# Acond_Elec.net
KiCad netlist of a schematic drawn in Altium Designer
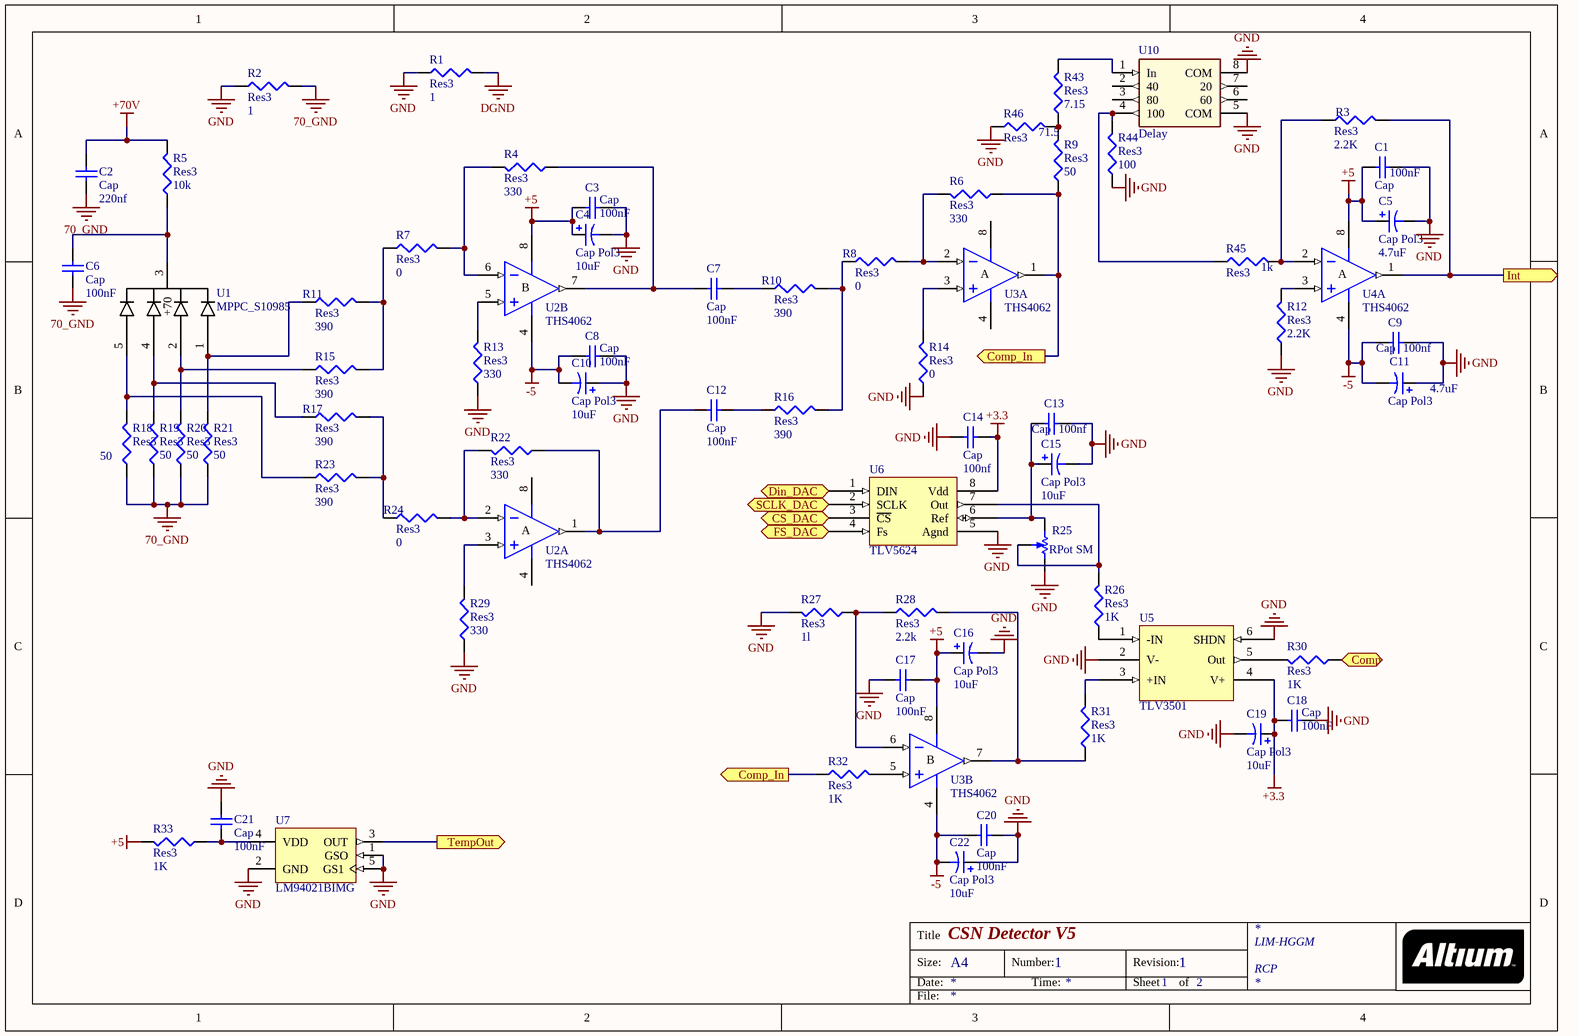
[diagram p0: Acond_Elec.SchDoc]

(export (version "E")
  (design (tool "Eeschema 10.0.6"))
  (components
    (comp (ref "C1")
      (value "Cap")
      (footprint "J1-0603")
      (description "Capacitor")
      (fields (field (name "ALTIUM_VALUE") "100nF") (field (name "PUBLISHER") "Altium Limited"))
      (libsource (lib "Miscellaneous Devices") (part "Cap"))
    )
    (comp (ref "C2")
      (value "Cap")
      (footprint "C0805")
      (description "Capacitor")
      (fields (field (name "ALTIUM_VALUE") "220nf") (field (name "PUBLISHER") "Altium Limited"))
      (libsource (lib "Miscellaneous Devices") (part "Cap"))
    )
    (comp (ref "C3")
      (value "Cap")
      (footprint "J1-0603")
      (description "Capacitor")
      (fields (field (name "ALTIUM_VALUE") "100nF") (field (name "PUBLISHER") "Altium Limited"))
      (libsource (lib "Miscellaneous Devices") (part "Cap"))
    )
    (comp (ref "C4")
      (value "Cap Pol3")
      (footprint "6-0805_N")
      (description "Polarized Capacitor (Surface Mount)")
      (fields (field (name "ALTIUM_VALUE") "10uF") (field (name "PUBLISHER") "Altium Limited"))
      (libsource (lib "Miscellaneous Devices") (part "Cap Pol3"))
    )
    (comp (ref "C5")
      (value "Cap Pol3")
      (footprint "6-0805_N")
      (description "Polarized Capacitor (Surface Mount)")
      (fields (field (name "ALTIUM_VALUE") "4.7uF") (field (name "PUBLISHER") "Altium Limited"))
      (libsource (lib "Miscellaneous Devices") (part "Cap Pol3"))
    )
    (comp (ref "C6")
      (value "Cap")
      (footprint "C0805")
      (description "Capacitor")
      (fields (field (name "ALTIUM_VALUE") "100nF") (field (name "PUBLISHER") "Altium Limited"))
      (libsource (lib "Miscellaneous Devices") (part "Cap"))
    )
    (comp (ref "C7")
      (value "Cap")
      (footprint "J1-0603")
      (description "Capacitor")
      (fields (field (name "ALTIUM_VALUE") "100nF") (field (name "PUBLISHER") "Altium Limited"))
      (libsource (lib "Miscellaneous Devices") (part "Cap"))
    )
    (comp (ref "C8")
      (value "Cap")
      (footprint "J1-0603")
      (description "Capacitor")
      (fields (field (name "ALTIUM_VALUE") "100nF") (field (name "PUBLISHER") "Altium Limited"))
      (libsource (lib "Miscellaneous Devices") (part "Cap"))
    )
    (comp (ref "C9")
      (value "Cap")
      (footprint "J1-0603")
      (description "Capacitor")
      (fields (field (name "ALTIUM_VALUE") "100nf") (field (name "PUBLISHER") "Altium Limited"))
      (libsource (lib "Miscellaneous Devices") (part "Cap"))
    )
    (comp (ref "C10")
      (value "Cap Pol3")
      (footprint "6-0805_N")
      (description "Polarized Capacitor (Surface Mount)")
      (fields (field (name "ALTIUM_VALUE") "10uF") (field (name "PUBLISHER") "Altium Limited"))
      (libsource (lib "Miscellaneous Devices") (part "Cap Pol3"))
    )
    (comp (ref "C11")
      (value "Cap Pol3")
      (footprint "6-0805_N")
      (description "Polarized Capacitor (Surface Mount)")
      (fields (field (name "ALTIUM_VALUE") "4.7uF") (field (name "PUBLISHER") "Altium Limited"))
      (libsource (lib "Miscellaneous Devices") (part "Cap Pol3"))
    )
    (comp (ref "C12")
      (value "Cap")
      (footprint "J1-0603")
      (description "Capacitor")
      (fields (field (name "ALTIUM_VALUE") "100nF") (field (name "PUBLISHER") "Altium Limited"))
      (libsource (lib "Miscellaneous Devices") (part "Cap"))
    )
    (comp (ref "C13")
      (value "Cap")
      (footprint "J1-0603")
      (description "Capacitor")
      (fields (field (name "ALTIUM_VALUE") "100nf") (field (name "PUBLISHER") "Altium Limited"))
      (libsource (lib "Miscellaneous Devices") (part "Cap"))
    )
    (comp (ref "C14")
      (value "Cap")
      (footprint "J1-0603")
      (description "Capacitor")
      (fields (field (name "ALTIUM_VALUE") "100nf") (field (name "PUBLISHER") "Altium Limited"))
      (libsource (lib "Miscellaneous Devices") (part "Cap"))
    )
    (comp (ref "C15")
      (value "Cap Pol3")
      (footprint "6-0805_N")
      (description "Polarized Capacitor (Surface Mount)")
      (fields (field (name "ALTIUM_VALUE") "10uF") (field (name "PUBLISHER") "Altium Limited"))
      (libsource (lib "Miscellaneous Devices") (part "Cap Pol3"))
    )
    (comp (ref "C16")
      (value "Cap Pol3")
      (footprint "6-0805_N")
      (description "Polarized Capacitor (Surface Mount)")
      (fields (field (name "ALTIUM_VALUE") "10uF") (field (name "PUBLISHER") "Altium Limited"))
      (libsource (lib "Miscellaneous Devices") (part "Cap Pol3"))
    )
    (comp (ref "C17")
      (value "Cap")
      (footprint "J1-0603")
      (description "Capacitor")
      (fields (field (name "ALTIUM_VALUE") "100nF") (field (name "PUBLISHER") "Altium Limited"))
      (libsource (lib "Miscellaneous Devices") (part "Cap"))
    )
    (comp (ref "C18")
      (value "Cap")
      (footprint "J1-0603")
      (description "Capacitor")
      (fields (field (name "ALTIUM_VALUE") "100nF") (field (name "PUBLISHER") "Altium Limited"))
      (libsource (lib "Miscellaneous Devices") (part "Cap"))
    )
    (comp (ref "C19")
      (value "Cap Pol3")
      (footprint "6-0805_N")
      (description "Polarized Capacitor (Surface Mount)")
      (fields (field (name "ALTIUM_VALUE") "10uF") (field (name "PUBLISHER") "Altium Limited"))
      (libsource (lib "Miscellaneous Devices") (part "Cap Pol3"))
    )
    (comp (ref "C20")
      (value "Cap")
      (footprint "J1-0603")
      (description "Capacitor")
      (fields (field (name "ALTIUM_VALUE") "100nF") (field (name "PUBLISHER") "Altium Limited"))
      (libsource (lib "Miscellaneous Devices") (part "Cap"))
    )
    (comp (ref "C21")
      (value "Cap")
      (footprint "6-0805_N")
      (description "Capacitor")
      (fields (field (name "ALTIUM_VALUE") "100nF") (field (name "PUBLISHER") "Altium Limited"))
      (libsource (lib "Miscellaneous Devices") (part "Cap"))
    )
    (comp (ref "C22")
      (value "Cap Pol3")
      (footprint "6-0805_N")
      (description "Polarized Capacitor (Surface Mount)")
      (fields (field (name "ALTIUM_VALUE") "10uF") (field (name "PUBLISHER") "Altium Limited"))
      (libsource (lib "Miscellaneous Devices") (part "Cap Pol3"))
    )
    (comp (ref "R1")
      (value "Res3")
      (footprint "J1-0603")
      (description "Resistor")
      (fields (field (name "ALTIUM_VALUE") "1") (field (name "PUBLISHER") "Altium Limited"))
      (libsource (lib "Miscellaneous Devices") (part "Res3"))
    )
    (comp (ref "R2")
      (value "Res3")
      (footprint "J1-0603")
      (description "Resistor")
      (fields (field (name "ALTIUM_VALUE") "1") (field (name "PUBLISHER") "Altium Limited"))
      (libsource (lib "Miscellaneous Devices") (part "Res3"))
    )
    (comp (ref "R3")
      (value "Res3")
      (footprint "J1-0603")
      (description "Resistor")
      (fields (field (name "ALTIUM_VALUE") "2.2K") (field (name "PUBLISHER") "Altium Limited"))
      (libsource (lib "Miscellaneous Devices") (part "Res3"))
    )
    (comp (ref "R4")
      (value "Res3")
      (footprint "J1-0603")
      (description "Resistor")
      (fields (field (name "ALTIUM_VALUE") "330") (field (name "PUBLISHER") "Altium Limited"))
      (libsource (lib "Miscellaneous Devices") (part "Res3"))
    )
    (comp (ref "R5")
      (value "Res3")
      (footprint "J1-0603")
      (description "Resistor")
      (fields (field (name "ALTIUM_VALUE") "10k") (field (name "PUBLISHER") "Altium Limited"))
      (libsource (lib "Miscellaneous Devices") (part "Res3"))
    )
    (comp (ref "R6")
      (value "Res3")
      (footprint "J1-0603")
      (description "Resistor")
      (fields (field (name "ALTIUM_VALUE") "330") (field (name "PUBLISHER") "Altium Limited"))
      (libsource (lib "Miscellaneous Devices") (part "Res3"))
    )
    (comp (ref "R7")
      (value "Res3")
      (footprint "J1-0603")
      (description "Resistor")
      (fields (field (name "ALTIUM_VALUE") "0") (field (name "PUBLISHER") "Altium Limited"))
      (libsource (lib "Miscellaneous Devices") (part "Res3"))
    )
    (comp (ref "R8")
      (value "Res3")
      (footprint "J1-0603")
      (description "Resistor")
      (fields (field (name "ALTIUM_VALUE") "0") (field (name "PUBLISHER") "Altium Limited"))
      (libsource (lib "Miscellaneous Devices") (part "Res3"))
    )
    (comp (ref "R9")
      (value "Res3")
      (footprint "J1-0603")
      (description "Resistor")
      (fields (field (name "ALTIUM_VALUE") "50") (field (name "PUBLISHER") "Altium Limited"))
      (libsource (lib "Miscellaneous Devices") (part "Res3"))
    )
    (comp (ref "R10")
      (value "Res3")
      (footprint "J1-0603")
      (description "Resistor")
      (fields (field (name "ALTIUM_VALUE") "390") (field (name "PUBLISHER") "Altium Limited"))
      (libsource (lib "Miscellaneous Devices") (part "Res3"))
    )
    (comp (ref "R11")
      (value "Res3")
      (footprint "J1-0603")
      (description "Resistor")
      (fields (field (name "ALTIUM_VALUE") "390") (field (name "PUBLISHER") "Altium Limited"))
      (libsource (lib "Miscellaneous Devices") (part "Res3"))
    )
    (comp (ref "R12")
      (value "Res3")
      (footprint "J1-0603")
      (description "Resistor")
      (fields (field (name "ALTIUM_VALUE") "2.2K") (field (name "PUBLISHER") "Altium Limited"))
      (libsource (lib "Miscellaneous Devices") (part "Res3"))
    )
    (comp (ref "R13")
      (value "Res3")
      (footprint "J1-0603")
      (description "Resistor")
      (fields (field (name "ALTIUM_VALUE") "330") (field (name "PUBLISHER") "Altium Limited"))
      (libsource (lib "Miscellaneous Devices") (part "Res3"))
    )
    (comp (ref "R14")
      (value "Res3")
      (footprint "J1-0603")
      (description "Resistor")
      (fields (field (name "ALTIUM_VALUE") "0") (field (name "PUBLISHER") "Altium Limited"))
      (libsource (lib "Miscellaneous Devices") (part "Res3"))
    )
    (comp (ref "R15")
      (value "Res3")
      (footprint "J1-0603")
      (description "Resistor")
      (fields (field (name "ALTIUM_VALUE") "390") (field (name "PUBLISHER") "Altium Limited"))
      (libsource (lib "Miscellaneous Devices") (part "Res3"))
    )
    (comp (ref "R16")
      (value "Res3")
      (footprint "J1-0603")
      (description "Resistor")
      (fields (field (name "ALTIUM_VALUE") "390") (field (name "PUBLISHER") "Altium Limited"))
      (libsource (lib "Miscellaneous Devices") (part "Res3"))
    )
    (comp (ref "R17")
      (value "Res3")
      (footprint "J1-0603")
      (description "Resistor")
      (fields (field (name "ALTIUM_VALUE") "390") (field (name "PUBLISHER") "Altium Limited"))
      (libsource (lib "Miscellaneous Devices") (part "Res3"))
    )
    (comp (ref "R18")
      (value "Res3")
      (footprint "J1-0603")
      (description "Resistor")
      (fields (field (name "ALTIUM_VALUE") "50") (field (name "PUBLISHER") "Altium Limited"))
      (libsource (lib "Miscellaneous Devices") (part "Res3"))
    )
    (comp (ref "R19")
      (value "Res3")
      (footprint "J1-0603")
      (description "Resistor")
      (fields (field (name "ALTIUM_VALUE") "50") (field (name "PUBLISHER") "Altium Limited"))
      (libsource (lib "Miscellaneous Devices") (part "Res3"))
    )
    (comp (ref "R20")
      (value "Res3")
      (footprint "J1-0603")
      (description "Resistor")
      (fields (field (name "ALTIUM_VALUE") "50") (field (name "PUBLISHER") "Altium Limited"))
      (libsource (lib "Miscellaneous Devices") (part "Res3"))
    )
    (comp (ref "R21")
      (value "Res3")
      (footprint "J1-0603")
      (description "Resistor")
      (fields (field (name "ALTIUM_VALUE") "50") (field (name "PUBLISHER") "Altium Limited"))
      (libsource (lib "Miscellaneous Devices") (part "Res3"))
    )
    (comp (ref "R22")
      (value "Res3")
      (footprint "J1-0603")
      (description "Resistor")
      (fields (field (name "ALTIUM_VALUE") "330") (field (name "PUBLISHER") "Altium Limited"))
      (libsource (lib "Miscellaneous Devices") (part "Res3"))
    )
    (comp (ref "R23")
      (value "Res3")
      (footprint "J1-0603")
      (description "Resistor")
      (fields (field (name "ALTIUM_VALUE") "390") (field (name "PUBLISHER") "Altium Limited"))
      (libsource (lib "Miscellaneous Devices") (part "Res3"))
    )
    (comp (ref "R24")
      (value "Res3")
      (footprint "J1-0603")
      (description "Resistor")
      (fields (field (name "ALTIUM_VALUE") "0") (field (name "PUBLISHER") "Altium Limited"))
      (libsource (lib "Miscellaneous Devices") (part "Res3"))
    )
    (comp (ref "R25")
      (value "RPot SM")
      (footprint "POT4MM-2")
      (description "Square Trimming Potentiometer")
      (fields (field (name "PUBLISHER") "Altium Limited"))
      (libsource (lib "Miscellaneous Devices") (part "RPot SM"))
    )
    (comp (ref "R26")
      (value "Res3")
      (footprint "J1-0603")
      (description "Resistor")
      (fields (field (name "ALTIUM_VALUE") "1K") (field (name "PUBLISHER") "Altium Limited"))
      (libsource (lib "Miscellaneous Devices") (part "Res3"))
    )
    (comp (ref "R27")
      (value "Res3")
      (footprint "J1-0603")
      (description "Resistor")
      (fields (field (name "ALTIUM_VALUE") "1l") (field (name "PUBLISHER") "Altium Limited"))
      (libsource (lib "Miscellaneous Devices") (part "Res3"))
    )
    (comp (ref "R28")
      (value "Res3")
      (footprint "J1-0603")
      (description "Resistor")
      (fields (field (name "ALTIUM_VALUE") "2.2k") (field (name "PUBLISHER") "Altium Limited"))
      (libsource (lib "Miscellaneous Devices") (part "Res3"))
    )
    (comp (ref "R29")
      (value "Res3")
      (footprint "J1-0603")
      (description "Resistor")
      (fields (field (name "ALTIUM_VALUE") "330") (field (name "PUBLISHER") "Altium Limited"))
      (libsource (lib "Miscellaneous Devices") (part "Res3"))
    )
    (comp (ref "R30")
      (value "Res3")
      (footprint "J1-0603")
      (description "Resistor")
      (fields (field (name "ALTIUM_VALUE") "1K") (field (name "PUBLISHER") "Altium Limited"))
      (libsource (lib "Miscellaneous Devices") (part "Res3"))
    )
    (comp (ref "R31")
      (value "Res3")
      (footprint "J1-0603")
      (description "Resistor")
      (fields (field (name "ALTIUM_VALUE") "1K") (field (name "PUBLISHER") "Altium Limited"))
      (libsource (lib "Miscellaneous Devices") (part "Res3"))
    )
    (comp (ref "R32")
      (value "Res3")
      (footprint "J1-0603")
      (description "Resistor")
      (fields (field (name "ALTIUM_VALUE") "1K") (field (name "PUBLISHER") "Altium Limited"))
      (libsource (lib "Miscellaneous Devices") (part "Res3"))
    )
    (comp (ref "R33")
      (value "Res3")
      (footprint "J1-0603")
      (description "Resistor")
      (fields (field (name "ALTIUM_VALUE") "1K") (field (name "PUBLISHER") "Altium Limited"))
      (libsource (lib "Miscellaneous Devices") (part "Res3"))
    )
    (comp (ref "R43")
      (value "Res3")
      (footprint "J1-0603")
      (description "Resistor")
      (fields (field (name "ALTIUM_VALUE") "7.15") (field (name "PUBLISHER") "Altium Limited"))
      (libsource (lib "Miscellaneous Devices") (part "Res3"))
    )
    (comp (ref "R44")
      (value "Res3")
      (footprint "J1-0603")
      (description "Resistor")
      (fields (field (name "ALTIUM_VALUE") "100") (field (name "PUBLISHER") "Altium Limited"))
      (libsource (lib "Miscellaneous Devices") (part "Res3"))
    )
    (comp (ref "R45")
      (value "Res3")
      (footprint "J1-0603")
      (description "Resistor")
      (fields (field (name "ALTIUM_VALUE") "1k") (field (name "PUBLISHER") "Altium Limited"))
      (libsource (lib "Miscellaneous Devices") (part "Res3"))
    )
    (comp (ref "R46")
      (value "Res3")
      (footprint "J1-0603")
      (description "Resistor")
      (fields (field (name "ALTIUM_VALUE") "71.5") (field (name "PUBLISHER") "Altium Limited"))
      (libsource (lib "Miscellaneous Devices") (part "Res3"))
    )
    (comp (ref "U1")
      (value "MPPC_S10985")
      (footprint "S10985_HAM")
      (libsource (lib "Int_Lib1") (part "MPPC_S10985"))
    )
    (comp (ref "U2")
      (value "THS4062")
      (footprint "SO-8_N")
      (description "Dual 600MHz, 50mW Current Feedback Amplifier")
      (fields (field (name "PUBLISHER") "Altium Limited"))
      (libsource (lib "AD Operational Amplifier") (part "AD8002AR"))
    )
    (comp (ref "U3")
      (value "THS4062")
      (footprint "SO-8_N")
      (description "Dual 600MHz, 50mW Current Feedback Amplifier")
      (fields (field (name "PUBLISHER") "Altium Limited"))
      (libsource (lib "AD Operational Amplifier") (part "AD8002AR"))
    )
    (comp (ref "U4")
      (value "THS4062")
      (footprint "SO-8_N")
      (description "Dual 600MHz, 50mW Current Feedback Amplifier")
      (fields (field (name "PUBLISHER") "Altium Limited"))
      (libsource (lib "AD Operational Amplifier") (part "AD8002AR"))
    )
    (comp (ref "U5")
      (value "TLV3501")
      (footprint "SOT23-6_N")
      (description "Analog Comparator")
      (libsource (lib "Int_Lib1") (part "TLV3501"))
    )
    (comp (ref "U6")
      (value "TLV5624")
      (footprint "SO-8_N")
      (description "DAC, internal reference, SPI")
      (libsource (lib "Int_Lib1") (part "TLV5624"))
    )
    (comp (ref "U7")
      (value "LM94021BIMG")
      (footprint "MAA05A_N")
      (description "Multi-Gain Analog Temperature Sensor, 5-pin SC-70")
      (fields
        (field (name "MANUFACTURER") "National Semiconductor")
        (field (name "PUBLISHER") "Altium Limited")
      )
      (libsource (lib "NSC Temperature Sensor") (part "LM94021BIMG"))
    )
    (comp (ref "U10") (value "Delay") (footprint "AMZ-G-SMD") (libsource (lib "Int_Lib1") (part "AMZ-601G")))
  )
  (nets
    (net (code "1") (name "+3.3") (class "Default")
      (node (ref "C14") (pin "1") (pinfunction "1_1") (pintype "passive"))
      (node (ref "C18") (pin "2") (pinfunction "2_2") (pintype "passive"))
      (node (ref "C19") (pin "1") (pinfunction "1_1") (pintype "passive"))
      (node (ref "U5") (pin "4") (pinfunction "V+_4") (pintype "power_in"))
      (node (ref "U6") (pin "8") (pinfunction "Vdd_8") (pintype "power_in"))
    )
    (net (code "2") (name "+5") (class "Default")
      (node (ref "C1") (pin "2") (pinfunction "2_2") (pintype "passive"))
      (node (ref "C16") (pin "1") (pinfunction "1_1") (pintype "passive"))
      (node (ref "C17") (pin "2") (pinfunction "2_2") (pintype "passive"))
      (node (ref "C3") (pin "2") (pinfunction "2_2") (pintype "passive"))
      (node (ref "C4") (pin "1") (pinfunction "1_1") (pintype "passive"))
      (node (ref "C5") (pin "1") (pinfunction "1_1") (pintype "passive"))
      (node (ref "R33") (pin "2") (pinfunction "2_2") (pintype "passive"))
      (node (ref "U2") (pin "8") (pinfunction "V+_8") (pintype "power_in"))
      (node (ref "U3") (pin "8") (pinfunction "V+_8") (pintype "power_in"))
      (node (ref "U4") (pin "8") (pinfunction "V+_8") (pintype "power_in"))
    )
    (net (code "3") (name "+70V") (class "Default")
      (node (ref "C2") (pin "2") (pinfunction "2_2") (pintype "passive"))
      (node (ref "R5") (pin "2") (pinfunction "2_2") (pintype "passive"))
    )
    (net (code "4") (name "-5") (class "Default")
      (node (ref "C10") (pin "2") (pinfunction "2_2") (pintype "passive"))
      (node (ref "C11") (pin "2") (pinfunction "2_2") (pintype "passive"))
      (node (ref "C20") (pin "1") (pinfunction "1_1") (pintype "passive"))
      (node (ref "C22") (pin "2") (pinfunction "2_2") (pintype "passive"))
      (node (ref "C8") (pin "2") (pinfunction "2_2") (pintype "passive"))
      (node (ref "C9") (pin "1") (pinfunction "1_1") (pintype "passive"))
      (node (ref "U2") (pin "4") (pinfunction "V-_4") (pintype "power_in"))
      (node (ref "U3") (pin "4") (pinfunction "V-_4") (pintype "power_in"))
      (node (ref "U4") (pin "4") (pinfunction "V-_4") (pintype "power_in"))
    )
    (net (code "5") (name "/CS_DAC") (class "Default")
      (node (ref "U6") (pin "3") (pinfunction "~{CS}_3") (pintype "passive"))
    )
    (net (code "6") (name "/Comp") (class "Default")
      (node (ref "R30") (pin "1") (pinfunction "1_1") (pintype "passive"))
    )
    (net (code "7") (name "/Comp_In") (class "Default")
      (node (ref "R32") (pin "1") (pinfunction "1_1") (pintype "passive"))
      (node (ref "R6") (pin "1") (pinfunction "1_1") (pintype "passive"))
      (node (ref "R9") (pin "1") (pinfunction "1_1") (pintype "passive"))
      (node (ref "U3") (pin "1") (pinfunction "OUT_1") (pintype "output"))
    )
    (net (code "8") (name "/Din_DAC") (class "Default")
      (node (ref "U6") (pin "1") (pinfunction "DIN_1") (pintype "input"))
    )
    (net (code "9") (name "/FS_DAC") (class "Default")
      (node (ref "U6") (pin "4") (pinfunction "Fs_4") (pintype "input"))
    )
    (net (code "10") (name "/Int") (class "Default")
      (node (ref "R3") (pin "2") (pinfunction "2_2") (pintype "passive"))
      (node (ref "U4") (pin "1") (pinfunction "OUT_1") (pintype "output"))
    )
    (net (code "11") (name "/SCLK_DAC") (class "Default")
      (node (ref "U6") (pin "2") (pinfunction "SCLK_2") (pintype "input"))
    )
    (net (code "12") (name "/TempOut") (class "Default")
      (node (ref "U7") (pin "3") (pinfunction "OUT_3") (pintype "output"))
    )
    (net (code "13") (name "70_GND") (class "Default")
      (node (ref "C2") (pin "1") (pinfunction "1_1") (pintype "passive"))
      (node (ref "C6") (pin "1") (pinfunction "1_1") (pintype "passive"))
      (node (ref "R18") (pin "1") (pinfunction "1_1") (pintype "passive"))
      (node (ref "R19") (pin "1") (pinfunction "1_1") (pintype "passive"))
      (node (ref "R2") (pin "2") (pinfunction "2_2") (pintype "passive"))
      (node (ref "R20") (pin "1") (pinfunction "1_1") (pintype "passive"))
      (node (ref "R21") (pin "1") (pinfunction "1_1") (pintype "passive"))
    )
    (net (code "14") (name "DGND") (class "Default")
      (node (ref "R1") (pin "2") (pinfunction "2_2") (pintype "passive"))
    )
    (net (code "15") (name "GND") (class "Default")
      (node (ref "C1") (pin "1") (pinfunction "1_1") (pintype "passive"))
      (node (ref "C10") (pin "1") (pinfunction "1_1") (pintype "passive"))
      (node (ref "C11") (pin "1") (pinfunction "1_1") (pintype "passive"))
      (node (ref "C13") (pin "2") (pinfunction "2_2") (pintype "passive"))
      (node (ref "C14") (pin "2") (pinfunction "2_2") (pintype "passive"))
      (node (ref "C15") (pin "2") (pinfunction "2_2") (pintype "passive"))
      (node (ref "C16") (pin "2") (pinfunction "2_2") (pintype "passive"))
      (node (ref "C17") (pin "1") (pinfunction "1_1") (pintype "passive"))
      (node (ref "C18") (pin "1") (pinfunction "1_1") (pintype "passive"))
      (node (ref "C19") (pin "2") (pinfunction "2_2") (pintype "passive"))
      (node (ref "C20") (pin "2") (pinfunction "2_2") (pintype "passive"))
      (node (ref "C21") (pin "1") (pinfunction "1_1") (pintype "passive"))
      (node (ref "C22") (pin "1") (pinfunction "1_1") (pintype "passive"))
      (node (ref "C3") (pin "1") (pinfunction "1_1") (pintype "passive"))
      (node (ref "C4") (pin "2") (pinfunction "2_2") (pintype "passive"))
      (node (ref "C5") (pin "2") (pinfunction "2_2") (pintype "passive"))
      (node (ref "C8") (pin "1") (pinfunction "1_1") (pintype "passive"))
      (node (ref "C9") (pin "2") (pinfunction "2_2") (pintype "passive"))
      (node (ref "R1") (pin "1") (pinfunction "1_1") (pintype "passive"))
      (node (ref "R12") (pin "1") (pinfunction "1_1") (pintype "passive"))
      (node (ref "R13") (pin "1") (pinfunction "1_1") (pintype "passive"))
      (node (ref "R14") (pin "1") (pinfunction "1_1") (pintype "passive"))
      (node (ref "R2") (pin "1") (pinfunction "1_1") (pintype "passive"))
      (node (ref "R25") (pin "CW") (pinfunction "+_CW") (pintype "passive"))
      (node (ref "R27") (pin "2") (pinfunction "2_2") (pintype "passive"))
      (node (ref "R29") (pin "1") (pinfunction "1_1") (pintype "passive"))
      (node (ref "R44") (pin "1") (pinfunction "1_1") (pintype "passive"))
      (node (ref "R46") (pin "1") (pinfunction "1_1") (pintype "passive"))
      (node (ref "U10") (pin "5") (pinfunction "COM_5") (pintype "power_in"))
      (node (ref "U10") (pin "8") (pinfunction "COM_8") (pintype "power_in"))
      (node (ref "U5") (pin "2") (pinfunction "V-_2") (pintype "power_in"))
      (node (ref "U5") (pin "6") (pinfunction "SHDN_6") (pintype "input"))
      (node (ref "U6") (pin "5") (pinfunction "Agnd_5") (pintype "power_in"))
      (node (ref "U7") (pin "1") (pinfunction "GSO_1") (pintype "input"))
      (node (ref "U7") (pin "2") (pinfunction "GND_2") (pintype "power_in"))
      (node (ref "U7") (pin "5") (pinfunction "GS1_5") (pintype "input"))
    )
    (net (code "16") (name "Net-(C7-Pad2)") (class "Default")
      (node (ref "C7") (pin "2") (pinfunction "2_2") (pintype "passive"))
      (node (ref "R10") (pin "1") (pinfunction "1_1") (pintype "passive"))
    )
    (net (code "17") (name "Net-(C12-Pad2)") (class "Default")
      (node (ref "C12") (pin "2") (pinfunction "2_2") (pintype "passive"))
      (node (ref "R16") (pin "1") (pinfunction "1_1") (pintype "passive"))
    )
    (net (code "18") (name "Net-(R10-Pad2)") (class "Default")
      (node (ref "R10") (pin "2") (pinfunction "2_2") (pintype "passive"))
      (node (ref "R16") (pin "2") (pinfunction "2_2") (pintype "passive"))
      (node (ref "R8") (pin "1") (pinfunction "1_1") (pintype "passive"))
    )
    (net (code "19") (name "Net-(R11-Pad2)") (class "Default")
      (node (ref "R11") (pin "2") (pinfunction "2_2") (pintype "passive"))
      (node (ref "R15") (pin "2") (pinfunction "2_2") (pintype "passive"))
      (node (ref "R7") (pin "1") (pinfunction "1_1") (pintype "passive"))
    )
    (net (code "20") (name "Net-(R17-Pad1)") (class "Default")
      (node (ref "R17") (pin "1") (pinfunction "1_1") (pintype "passive"))
      (node (ref "R19") (pin "2") (pinfunction "2_2") (pintype "passive"))
      (node (ref "U1") (pin "4") (pinfunction "4_4") (pintype "passive"))
    )
    (net (code "21") (name "Net-(R17-Pad2)") (class "Default")
      (node (ref "R17") (pin "2") (pinfunction "2_2") (pintype "passive"))
      (node (ref "R23") (pin "2") (pinfunction "2_2") (pintype "passive"))
      (node (ref "R24") (pin "1") (pinfunction "1_1") (pintype "passive"))
    )
    (net (code "22") (name "Net-(R18-Pad2)") (class "Default")
      (node (ref "R18") (pin "2") (pinfunction "2_2") (pintype "passive"))
      (node (ref "R23") (pin "1") (pinfunction "1_1") (pintype "passive"))
      (node (ref "U1") (pin "5") (pinfunction "5_5") (pintype "passive"))
    )
    (net (code "23") (name "Net-(R25--)") (class "Default")
      (node (ref "C13") (pin "1") (pinfunction "1_1") (pintype "passive"))
      (node (ref "C15") (pin "1") (pinfunction "1_1") (pintype "passive"))
      (node (ref "R25") (pin "CCW") (pinfunction "-_CCW") (pintype "passive"))
      (node (ref "U6") (pin "6") (pinfunction "Ref_6") (pintype "bidirectional"))
    )
    (net (code "24") (name "Net-(R43-Pad1)") (class "Default")
      (node (ref "R43") (pin "1") (pinfunction "1_1") (pintype "passive"))
      (node (ref "R46") (pin "2") (pinfunction "2_2") (pintype "passive"))
      (node (ref "R9") (pin "2") (pinfunction "2_2") (pintype "passive"))
    )
    (net (code "25") (name "Net-(U1-+70)") (class "Default")
      (node (ref "C6") (pin "2") (pinfunction "2_2") (pintype "passive"))
      (node (ref "R5") (pin "1") (pinfunction "1_1") (pintype "passive"))
      (node (ref "U1") (pin "3") (pinfunction "+70_3") (pintype "passive"))
    )
    (net (code "26") (name "Net-(U1-Pin1)") (class "Default")
      (node (ref "R11") (pin "1") (pinfunction "1_1") (pintype "passive"))
      (node (ref "R21") (pin "2") (pinfunction "2_2") (pintype "passive"))
      (node (ref "U1") (pin "1") (pinfunction "Pin1_1") (pintype "passive"))
    )
    (net (code "27") (name "Net-(U1-Pin2)") (class "Default")
      (node (ref "R15") (pin "1") (pinfunction "1_1") (pintype "passive"))
      (node (ref "R20") (pin "2") (pinfunction "2_2") (pintype "passive"))
      (node (ref "U1") (pin "2") (pinfunction "Pin2_2") (pintype "passive"))
    )
    (net (code "28") (name "Net-(U2A-IN+)") (class "Default")
      (node (ref "R29") (pin "2") (pinfunction "2_2") (pintype "passive"))
      (node (ref "U2") (pin "3") (pinfunction "IN+_3") (pintype "input"))
    )
    (net (code "29") (name "Net-(U2A-IN-)") (class "Default")
      (node (ref "R22") (pin "2") (pinfunction "2_2") (pintype "passive"))
      (node (ref "R24") (pin "2") (pinfunction "2_2") (pintype "passive"))
      (node (ref "U2") (pin "2") (pinfunction "IN-_2") (pintype "input"))
    )
    (net (code "30") (name "Net-(U2A-OUT)") (class "Default")
      (node (ref "C12") (pin "1") (pinfunction "1_1") (pintype "passive"))
      (node (ref "R22") (pin "1") (pinfunction "1_1") (pintype "passive"))
      (node (ref "U2") (pin "1") (pinfunction "OUT_1") (pintype "output"))
    )
    (net (code "31") (name "Net-(U2B-IN+)") (class "Default")
      (node (ref "R13") (pin "2") (pinfunction "2_2") (pintype "passive"))
      (node (ref "U2") (pin "5") (pinfunction "IN+_5") (pintype "input"))
    )
    (net (code "32") (name "Net-(U2B-IN-)") (class "Default")
      (node (ref "R4") (pin "2") (pinfunction "2_2") (pintype "passive"))
      (node (ref "R7") (pin "2") (pinfunction "2_2") (pintype "passive"))
      (node (ref "U2") (pin "6") (pinfunction "IN-_6") (pintype "input"))
    )
    (net (code "33") (name "Net-(U2B-OUT)") (class "Default")
      (node (ref "C7") (pin "1") (pinfunction "1_1") (pintype "passive"))
      (node (ref "R4") (pin "1") (pinfunction "1_1") (pintype "passive"))
      (node (ref "U2") (pin "7") (pinfunction "OUT_7") (pintype "output"))
    )
    (net (code "34") (name "Net-(U3A-IN+)") (class "Default")
      (node (ref "R14") (pin "2") (pinfunction "2_2") (pintype "passive"))
      (node (ref "U3") (pin "3") (pinfunction "IN+_3") (pintype "input"))
    )
    (net (code "35") (name "Net-(U3A-IN-)") (class "Default")
      (node (ref "R6") (pin "2") (pinfunction "2_2") (pintype "passive"))
      (node (ref "R8") (pin "2") (pinfunction "2_2") (pintype "passive"))
      (node (ref "U3") (pin "2") (pinfunction "IN-_2") (pintype "input"))
    )
    (net (code "36") (name "Net-(U3B-IN+)") (class "Default")
      (node (ref "R32") (pin "2") (pinfunction "2_2") (pintype "passive"))
      (node (ref "U3") (pin "5") (pinfunction "IN+_5") (pintype "input"))
    )
    (net (code "37") (name "Net-(U3B-IN-)") (class "Default")
      (node (ref "R27") (pin "1") (pinfunction "1_1") (pintype "passive"))
      (node (ref "R28") (pin "1") (pinfunction "1_1") (pintype "passive"))
      (node (ref "U3") (pin "6") (pinfunction "IN-_6") (pintype "input"))
    )
    (net (code "38") (name "Net-(U3B-OUT)") (class "Default")
      (node (ref "R28") (pin "2") (pinfunction "2_2") (pintype "passive"))
      (node (ref "R31") (pin "1") (pinfunction "1_1") (pintype "passive"))
      (node (ref "U3") (pin "7") (pinfunction "OUT_7") (pintype "output"))
    )
    (net (code "39") (name "Net-(U4A-IN+)") (class "Default")
      (node (ref "R12") (pin "2") (pinfunction "2_2") (pintype "passive"))
      (node (ref "U4") (pin "3") (pinfunction "IN+_3") (pintype "input"))
    )
    (net (code "40") (name "Net-(U4A-IN-)") (class "Default")
      (node (ref "R3") (pin "1") (pinfunction "1_1") (pintype "passive"))
      (node (ref "R45") (pin "2") (pinfunction "2_2") (pintype "passive"))
      (node (ref "U4") (pin "2") (pinfunction "IN-_2") (pintype "input"))
    )
    (net (code "41") (name "Net-(U5-+IN)") (class "Default")
      (node (ref "R31") (pin "2") (pinfunction "2_2") (pintype "passive"))
      (node (ref "U5") (pin "3") (pinfunction "+IN_3") (pintype "input"))
    )
    (net (code "42") (name "Net-(U5--IN)") (class "Default")
      (node (ref "R26") (pin "1") (pinfunction "1_1") (pintype "passive"))
      (node (ref "U5") (pin "1") (pinfunction "-IN_1") (pintype "input"))
    )
    (net (code "43") (name "Net-(U5-Out)") (class "Default")
      (node (ref "R30") (pin "2") (pinfunction "2_2") (pintype "passive"))
      (node (ref "U5") (pin "5") (pinfunction "Out_5") (pintype "output"))
    )
    (net (code "44") (name "Net-(U6-Out)") (class "Default")
      (node (ref "R25") (pin "W") (pinfunction "W_W") (pintype "passive"))
      (node (ref "R26") (pin "2") (pinfunction "2_2") (pintype "passive"))
      (node (ref "U6") (pin "7") (pinfunction "Out_7") (pintype "output"))
    )
    (net (code "45") (name "Net-(U7-VDD)") (class "Default")
      (node (ref "C21") (pin "2") (pinfunction "2_2") (pintype "passive"))
      (node (ref "R33") (pin "1") (pinfunction "1_1") (pintype "passive"))
      (node (ref "U7") (pin "4") (pinfunction "VDD_4") (pintype "power_in"))
    )
    (net (code "46") (name "Net-(U10-100)") (class "Default")
      (node (ref "R44") (pin "2") (pinfunction "2_2") (pintype "passive"))
      (node (ref "R45") (pin "1") (pinfunction "1_1") (pintype "passive"))
      (node (ref "U10") (pin "4") (pinfunction "100_4") (pintype "output"))
    )
    (net (code "47") (name "Net-(U10-In)") (class "Default")
      (node (ref "R43") (pin "2") (pinfunction "2_2") (pintype "passive"))
      (node (ref "U10") (pin "1") (pinfunction "In_1") (pintype "input"))
    )
    (net (code "48") (name "unconnected-(U2A-V+-Pad8)") (class "Default")
      (node (ref "U2") (pin "8") (pinfunction "V+_8") (pintype "power_in"))
    )
    (net (code "49") (name "unconnected-(U2A-V--Pad4)") (class "Default")
      (node (ref "U2") (pin "4") (pinfunction "V-_4") (pintype "power_in"))
    )
    (net (code "50") (name "unconnected-(U3A-V+-Pad8)") (class "Default")
      (node (ref "U3") (pin "8") (pinfunction "V+_8") (pintype "power_in"))
    )
    (net (code "51") (name "unconnected-(U3A-V--Pad4)") (class "Default")
      (node (ref "U3") (pin "4") (pinfunction "V-_4") (pintype "power_in"))
    )
    (net (code "52") (name "unconnected-(U10-20-Pad7)") (class "Default")
      (node (ref "U10") (pin "7") (pinfunction "20_7") (pintype "output"))
    )
    (net (code "53") (name "unconnected-(U10-40-Pad2)") (class "Default")
      (node (ref "U10") (pin "2") (pinfunction "40_2") (pintype "output"))
    )
    (net (code "54") (name "unconnected-(U10-60-Pad6)") (class "Default")
      (node (ref "U10") (pin "6") (pinfunction "60_6") (pintype "output"))
    )
    (net (code "55") (name "unconnected-(U10-80-Pad3)") (class "Default")
      (node (ref "U10") (pin "3") (pinfunction "80_3") (pintype "output"))
    )
  )
)
